# Supply.net
KiCad netlist of a schematic drawn in Altium Designer
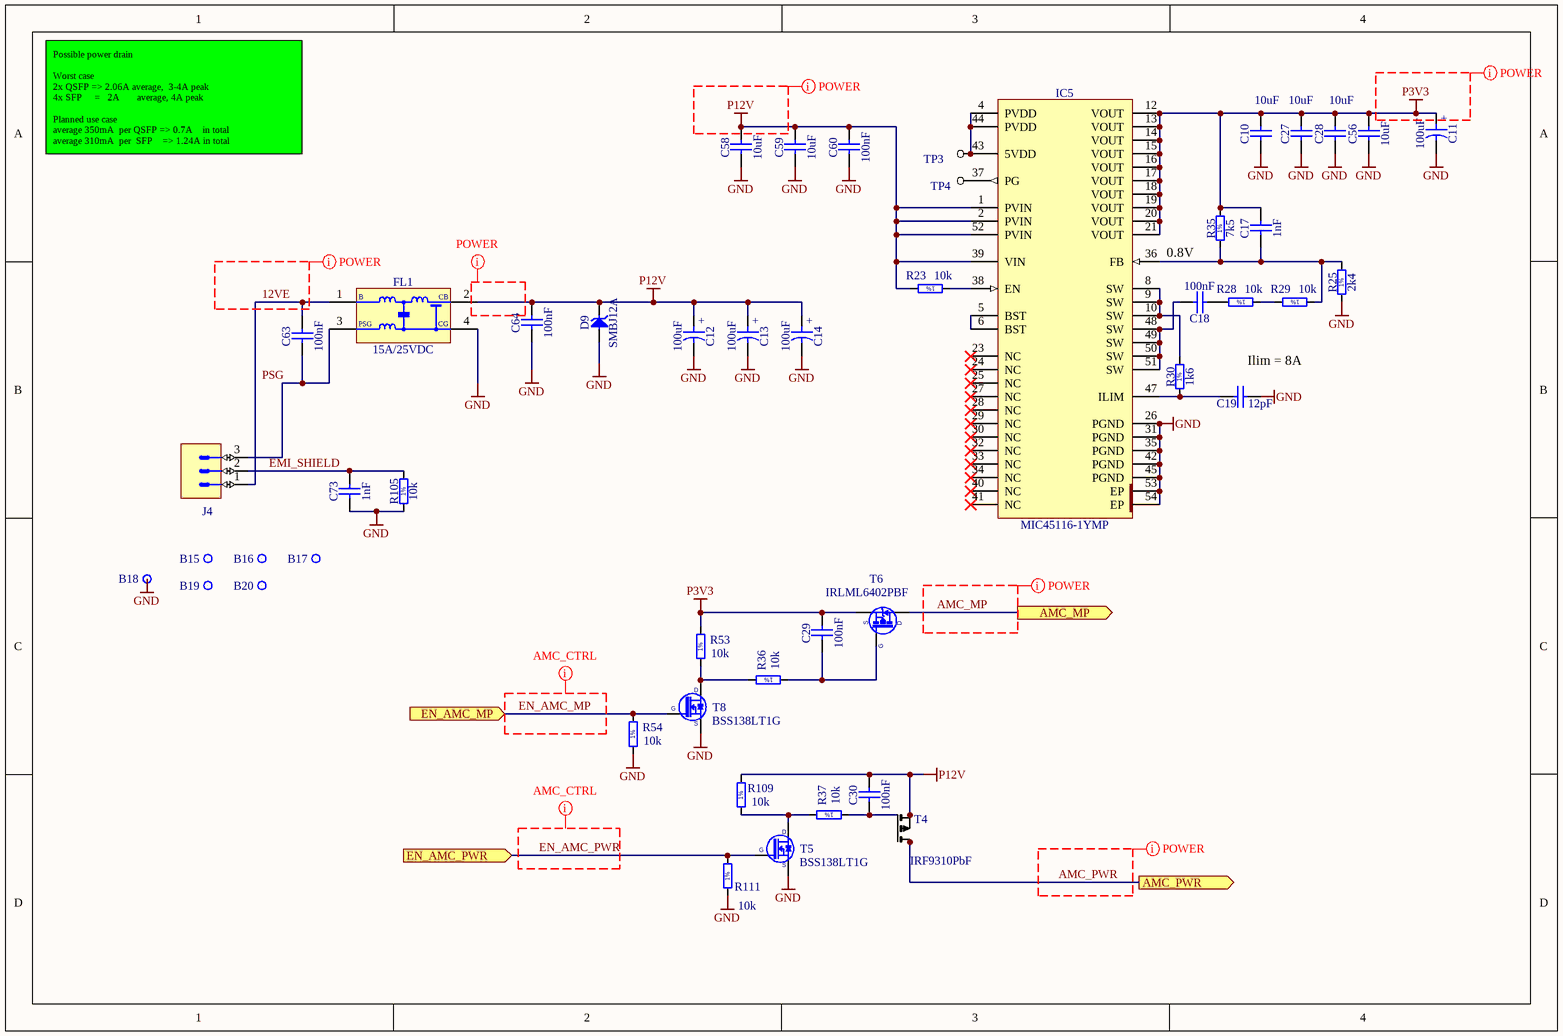
[diagram p0: Supply.SchDoc]

(export (version "E")
  (design (tool "Eeschema 10.0.6"))
  (components
    (comp (ref "B15")
      (value "Plated Hole")
      (footprint "MTG320_550")
      (description "Single Terminal Socket")
      (fields (field (name "PART NUMBER") "PLATED_HOLE3.2_PAD5.5") (field (name "AUTHOR") "CERN DEM JMW"))
      (libsource (lib "Eletro-mechanical") (part "Single Terminal Socket"))
    )
    (comp (ref "B16")
      (value "Plated Hole")
      (footprint "MTG320_550")
      (description "Single Terminal Socket")
      (fields (field (name "PART NUMBER") "PLATED_HOLE3.2_PAD5.5") (field (name "AUTHOR") "CERN DEM JMW"))
      (libsource (lib "Eletro-mechanical") (part "Single Terminal Socket"))
    )
    (comp (ref "B17")
      (value "Plated Hole")
      (footprint "MTG320_550")
      (description "Single Terminal Socket")
      (fields (field (name "PART NUMBER") "PLATED_HOLE3.2_PAD5.5") (field (name "AUTHOR") "CERN DEM JMW"))
      (libsource (lib "Eletro-mechanical") (part "Single Terminal Socket"))
    )
    (comp (ref "B18")
      (value "Plated Hole")
      (footprint "MTG320_550")
      (description "Single Terminal Socket")
      (fields (field (name "PART NUMBER") "PLATED_HOLE3.2_PAD5.5") (field (name "AUTHOR") "CERN DEM JMW"))
      (libsource (lib "Eletro-mechanical") (part "Single Terminal Socket"))
    )
    (comp (ref "B19")
      (value "Plated Hole")
      (footprint "MTG320_550")
      (description "Single Terminal Socket")
      (fields (field (name "PART NUMBER") "PLATED_HOLE3.2_PAD5.5") (field (name "AUTHOR") "CERN DEM JMW"))
      (libsource (lib "Eletro-mechanical") (part "Single Terminal Socket"))
    )
    (comp (ref "B20")
      (value "Plated Hole")
      (footprint "MTG320_550")
      (description "Single Terminal Socket")
      (fields (field (name "PART NUMBER") "PLATED_HOLE3.2_PAD5.5") (field (name "AUTHOR") "CERN DEM JMW"))
      (libsource (lib "Eletro-mechanical") (part "Single Terminal Socket"))
    )
    (comp (ref "C10")
      (value "10uF")
      (footprint "CAPC2012X135N")
      (description "Non-polarised capacitor")
      (fields
        (field (name "PART NUMBER") "CC0805_10UF_10V_10%_X7R")
        (field (name "VOLTAGE") "10V")
        (field (name "AUTHOR") "CERN DEM JLC")
      )
      (libsource (lib "Capacitors") (part "Capacitor - non polarized"))
    )
    (comp (ref "C11")
      (value "100uF")
      (footprint "CAPAE660X540N")
      (description "Polarised capacitor")
      (fields
        (field (name "PART NUMBER") "CAE660-540_100UF_16V_20%")
        (field (name "VOLTAGE") "16V")
        (field (name "AUTHOR") "CERN DEM JLC")
      )
      (libsource (lib "Capacitors") (part "Capacitor - polarized"))
    )
    (comp (ref "C12")
      (value "100uF")
      (footprint "CAPAE660X540N")
      (description "Polarised capacitor")
      (fields
        (field (name "PART NUMBER") "CAE660-540_100UF_16V_20%")
        (field (name "VOLTAGE") "16V")
        (field (name "AUTHOR") "CERN DEM JLC")
      )
      (libsource (lib "Capacitors") (part "Capacitor - polarized"))
    )
    (comp (ref "C13")
      (value "100uF")
      (footprint "CAPAE660X540N")
      (description "Polarised capacitor")
      (fields
        (field (name "PART NUMBER") "CAE660-540_100UF_16V_20%")
        (field (name "VOLTAGE") "16V")
        (field (name "AUTHOR") "CERN DEM JLC")
      )
      (libsource (lib "Capacitors") (part "Capacitor - polarized"))
    )
    (comp (ref "C14")
      (value "100uF")
      (footprint "CAPAE660X540N")
      (description "Polarised capacitor")
      (fields
        (field (name "PART NUMBER") "CAE660-540_100UF_16V_20%")
        (field (name "VOLTAGE") "16V")
        (field (name "AUTHOR") "CERN DEM JLC")
      )
      (libsource (lib "Capacitors") (part "Capacitor - polarized"))
    )
    (comp (ref "C17")
      (value "1nF")
      (footprint "CAPC1005X55N")
      (description "Non-polarised capacitor")
      (fields
        (field (name "PART NUMBER") "CC0402_1NF_50V_10%_X7R")
        (field (name "VOLTAGE") "50V")
        (field (name "AUTHOR") "CERN DEM JLC")
      )
      (libsource (lib "Capacitors") (part "Capacitor - non polarized"))
    )
    (comp (ref "C18")
      (value "100nF")
      (footprint "CAPC1005X55N")
      (description "Non-polarised capacitor")
      (fields
        (field (name "PART NUMBER") "CC0402_100NF_16V_10%_X5R")
        (field (name "VOLTAGE") "16V")
        (field (name "AUTHOR") "CERN DEM JLC")
      )
      (libsource (lib "Capacitors") (part "Capacitor - non polarized"))
    )
    (comp (ref "C19")
      (value "12pF")
      (footprint "CAPC1005X55N")
      (description "Non-polarised capacitor")
      (fields
        (field (name "PART NUMBER") "CC0402_12PF_50V_5%_C0G")
        (field (name "VOLTAGE") "50V")
        (field (name "AUTHOR") "CERN DEM JLC")
      )
      (libsource (lib "Capacitors") (part "Capacitor - non polarized"))
    )
    (comp (ref "C27")
      (value "10uF")
      (footprint "CAPC2012X135N")
      (description "Non-polarised capacitor")
      (fields
        (field (name "PART NUMBER") "CC0805_10UF_10V_10%_X7R")
        (field (name "VOLTAGE") "10V")
        (field (name "AUTHOR") "CERN DEM JLC")
      )
      (libsource (lib "Capacitors") (part "Capacitor - non polarized"))
    )
    (comp (ref "C28")
      (value "10uF")
      (footprint "CAPC2012X135N")
      (description "Non-polarised capacitor")
      (fields
        (field (name "PART NUMBER") "CC0805_10UF_10V_10%_X7R")
        (field (name "VOLTAGE") "10V")
        (field (name "AUTHOR") "CERN DEM JLC")
      )
      (libsource (lib "Capacitors") (part "Capacitor - non polarized"))
    )
    (comp (ref "C29")
      (value "100nF")
      (footprint "CAPC1005X55N")
      (description "Non-polarised capacitor")
      (fields
        (field (name "PART NUMBER") "CC0402_100NF_16V_10%_X5R")
        (field (name "VOLTAGE") "16V")
        (field (name "AUTHOR") "CERN DEM JLC")
      )
      (libsource (lib "Capacitors") (part "Capacitor - non polarized"))
    )
    (comp (ref "C30")
      (value "100nF")
      (footprint "CAPC1005X55N")
      (description "Non-polarised capacitor")
      (fields
        (field (name "PART NUMBER") "CC0402_100NF_16V_10%_X5R")
        (field (name "VOLTAGE") "16V")
        (field (name "AUTHOR") "CERN DEM JLC")
      )
      (libsource (lib "Capacitors") (part "Capacitor - non polarized"))
    )
    (comp (ref "C56")
      (value "10uF")
      (footprint "CAPC2012X135N")
      (description "Non-polarised capacitor")
      (fields
        (field (name "PART NUMBER") "CC0805_10UF_10V_10%_X7R")
        (field (name "VOLTAGE") "10V")
        (field (name "AUTHOR") "CERN DEM JLC")
      )
      (libsource (lib "Capacitors") (part "Capacitor - non polarized"))
    )
    (comp (ref "C58")
      (value "10uF")
      (footprint "CAPC3216X140N")
      (description "Non-polarised capacitor")
      (fields
        (field (name "PART NUMBER") "CC1206_10UF_16V_10%_X7R")
        (field (name "VOLTAGE") "16V")
        (field (name "AUTHOR") "CERN DEM JLC")
      )
      (libsource (lib "Capacitors") (part "Capacitor - non polarized"))
    )
    (comp (ref "C59")
      (value "10uF")
      (footprint "CAPC3216X140N")
      (description "Non-polarised capacitor")
      (fields
        (field (name "PART NUMBER") "CC1206_10UF_16V_10%_X7R")
        (field (name "VOLTAGE") "16V")
        (field (name "AUTHOR") "CERN DEM JLC")
      )
      (libsource (lib "Capacitors") (part "Capacitor - non polarized"))
    )
    (comp (ref "C60")
      (value "100nF")
      (footprint "CAPC1005X55N")
      (description "Non-polarised capacitor")
      (fields
        (field (name "PART NUMBER") "CC0402_100NF_16V_10%_X5R")
        (field (name "VOLTAGE") "16V")
        (field (name "AUTHOR") "CERN DEM JLC")
      )
      (libsource (lib "Capacitors") (part "Capacitor - non polarized"))
    )
    (comp (ref "C63")
      (value "100nF")
      (footprint "CAPC1005X55N")
      (description "Non-polarised capacitor")
      (fields
        (field (name "PART NUMBER") "CC0402_100NF_16V_10%_X5R")
        (field (name "VOLTAGE") "16V")
        (field (name "AUTHOR") "CERN DEM JLC")
      )
      (libsource (lib "Capacitors") (part "Capacitor - non polarized"))
    )
    (comp (ref "C64")
      (value "100nF")
      (footprint "CAPC1005X55N")
      (description "Non-polarised capacitor")
      (fields
        (field (name "PART NUMBER") "CC0402_100NF_16V_10%_X5R")
        (field (name "VOLTAGE") "16V")
        (field (name "AUTHOR") "CERN DEM JLC")
      )
      (libsource (lib "Capacitors") (part "Capacitor - non polarized"))
    )
    (comp (ref "C73")
      (value "1nF")
      (footprint "CAPC1005X55N")
      (description "Non-polarised capacitor")
      (fields
        (field (name "PART NUMBER") "CC0402_1NF_50V_10%_X7R")
        (field (name "VOLTAGE") "50V")
        (field (name "AUTHOR") "CERN DEM JLC")
      )
      (libsource (lib "Capacitors") (part "Capacitor - non polarized"))
    )
    (comp (ref "D9")
      (value "SMBJ12A")
      (footprint "DIOM5336X265N")
      (description "Zener Diode")
      (fields
        (field (name "VOLTAGE") "12V")
        (field (name "POWER") "600W")
        (field (name "AUTHOR") "CERN DEM JLC")
      )
      (libsource (lib "ICs And Semiconductors") (part "Diode Zener"))
    )
    (comp (ref "FL1")
      (value "15A/25VDC")
      (footprint "FIL_MURATA_BNX016")
      (description "Block Type EMIFIL (LC Combined) SMD Type, BNX01* Serie")
      (fields
        (field (name "PART NUMBER") "FIL_MURATA_BNX016-01")
        (field (name "MANUFACTURER") "MURATA")
        (field (name "AUTHOR") "CERN DEM JLC")
      )
      (libsource (lib "Inductors & Transformers") (part "FIL_MURATA_BNX016"))
    )
    (comp (ref "IC5")
      (value "MIC45116-1YMP")
      (footprint "MICROCHIP_H3QFN88-52LD-PL-3")
      (description "0.8V to 85% PVIN (4.75-19V), 6A Synchronous Step-Down Regulator Module")
      (fields (field (name "MANUFACTURER") "MICROCHIP TECHNOLOGY") (field (name "AUTHOR") "CERN DEM JMW"))
      (libsource (lib "ICs And Semiconductors") (part "MIC45116"))
    )
    (comp (ref "J4")
      (value "~")
      (footprint "PHOENIX_1755749")
      (description "Connector 3 Male")
      (fields
        (field (name "PART NUMBER") "PHOENIX_1755749")
        (field (name "MANUFACTURER") "PHOENIX CONTACT")
        (field (name "AUTHOR") "CERN DEM JLC")
      )
      (libsource (lib "Connectors") (part "Connector 3 Male"))
    )
    (comp (ref "R23")
      (value "10k")
      (footprint "RESC1005X40N")
      (description "Resistor - 1%")
      (fields
        (field (name "PART NUMBER") "R0402_10K_1%_0.0625W_100PPM")
        (field (name "POWER") "0.0625W")
        (field (name "AUTHOR") "CERN DEM JLC")
      )
      (libsource (lib "Resistors") (part "Resistor - 1%"))
    )
    (comp (ref "R25")
      (value "2k4")
      (footprint "RESC1005X40N")
      (description "Resistor - 1%")
      (fields
        (field (name "PART NUMBER") "R0402_2K4_1%_0.0625W_100PPM")
        (field (name "POWER") "0.0625W")
        (field (name "AUTHOR") "CERN DEM JLC")
      )
      (libsource (lib "Resistors") (part "Resistor - 1%"))
    )
    (comp (ref "R28")
      (value "10k")
      (footprint "RESC1005X40N")
      (description "Resistor - 1%")
      (fields
        (field (name "PART NUMBER") "R0402_10K_1%_0.0625W_100PPM")
        (field (name "POWER") "0.0625W")
        (field (name "AUTHOR") "CERN DEM JLC")
      )
      (libsource (lib "Resistors") (part "Resistor - 1%"))
    )
    (comp (ref "R29")
      (value "10k")
      (footprint "RESC1005X40N")
      (description "Resistor - 1%")
      (fields
        (field (name "PART NUMBER") "R0402_10K_1%_0.0625W_100PPM")
        (field (name "POWER") "0.0625W")
        (field (name "AUTHOR") "CERN DEM JLC")
      )
      (libsource (lib "Resistors") (part "Resistor - 1%"))
    )
    (comp (ref "R30")
      (value "1k6")
      (footprint "RESC1005X40N")
      (description "Resistor - 1%")
      (fields
        (field (name "PART NUMBER") "R0402_1K6_1%_0.0625W_100PPM")
        (field (name "POWER") "0.0625W")
        (field (name "AUTHOR") "CERN DEM JLC")
      )
      (libsource (lib "Resistors") (part "Resistor - 1%"))
    )
    (comp (ref "R35")
      (value "7k5")
      (footprint "RESC1005X40N")
      (description "Resistor - 1%")
      (fields
        (field (name "PART NUMBER") "R0402_7K5_1%_0.0625W_100PPM")
        (field (name "POWER") "0.0625W")
        (field (name "AUTHOR") "CERN DEM JLC")
      )
      (libsource (lib "Resistors") (part "Resistor - 1%"))
    )
    (comp (ref "R36")
      (value "10k")
      (footprint "RESC1005X40N")
      (description "Resistor - 1%")
      (fields
        (field (name "PART NUMBER") "R0402_10K_1%_0.0625W_100PPM")
        (field (name "POWER") "0.0625W")
        (field (name "AUTHOR") "CERN DEM JLC")
      )
      (libsource (lib "Resistors") (part "Resistor - 1%"))
    )
    (comp (ref "R37")
      (value "10k")
      (footprint "RESC1005X40N")
      (description "Resistor - 1%")
      (fields
        (field (name "PART NUMBER") "R0402_10K_1%_0.0625W_100PPM")
        (field (name "POWER") "0.0625W")
        (field (name "AUTHOR") "CERN DEM JLC")
      )
      (libsource (lib "Resistors") (part "Resistor - 1%"))
    )
    (comp (ref "R53")
      (value "10k")
      (footprint "RESC1005X40N")
      (description "Resistor - 1%")
      (fields
        (field (name "PART NUMBER") "R0402_10K_1%_0.0625W_100PPM")
        (field (name "POWER") "0.0625W")
        (field (name "AUTHOR") "CERN DEM JLC")
      )
      (libsource (lib "Resistors") (part "Resistor - 1%"))
    )
    (comp (ref "R54")
      (value "10k")
      (footprint "RESC1005X40N")
      (description "Resistor - 1%")
      (fields
        (field (name "PART NUMBER") "R0402_10K_1%_0.0625W_100PPM")
        (field (name "POWER") "0.0625W")
        (field (name "AUTHOR") "CERN DEM JLC")
      )
      (libsource (lib "Resistors") (part "Resistor - 1%"))
    )
    (comp (ref "R105")
      (value "10k")
      (footprint "RESC1005X40N")
      (description "Resistor - 1%")
      (fields
        (field (name "PART NUMBER") "R0402_10K_1%_0.0625W_100PPM")
        (field (name "POWER") "0.0625W")
        (field (name "AUTHOR") "CERN DEM JLC")
      )
      (libsource (lib "Resistors") (part "Resistor - 1%"))
    )
    (comp (ref "R109")
      (value "10k")
      (footprint "RESC1005X40N")
      (description "Resistor - 1%")
      (fields
        (field (name "PART NUMBER") "R0402_10K_1%_0.0625W_100PPM")
        (field (name "POWER") "0.0625W")
        (field (name "AUTHOR") "CERN DEM JLC")
      )
      (libsource (lib "Resistors") (part "Resistor - 1%"))
    )
    (comp (ref "R111")
      (value "10k")
      (footprint "RESC1005X40N")
      (description "Resistor - 1%")
      (fields
        (field (name "PART NUMBER") "R0402_10K_1%_0.0625W_100PPM")
        (field (name "POWER") "0.0625W")
        (field (name "AUTHOR") "CERN DEM JLC")
      )
      (libsource (lib "Resistors") (part "Resistor - 1%"))
    )
    (comp (ref "T4")
      (value "IRF9310PbF")
      (footprint "so-8")
      (description "PMOS 30V, 4.6mR, 20A, 2.5W")
      (libsource (lib "LIBRARY_SCH") (part "Q_IRF9310"))
    )
    (comp (ref "T5")
      (value "BSS138LT1G")
      (footprint "SOT95P240X110-3N")
      (description "N-CHANNEL MOSFET WITH DIODE")
      (fields (field (name "MANUFACTURER") "ON SEMICONDUCTOR") (field (name "AUTHOR") "CERN DEM JLC"))
      (libsource (lib "ICs And Semiconductors") (part "N-MOSFET-D 1G 2S 3D"))
    )
    (comp (ref "T6")
      (value "IRLML6402PBF")
      (footprint "SOT95P237X112-3N")
      (description "P-CHANNEL MOSFET WITH ZENER DIODE")
      (fields (field (name "MANUFACTURER") "INTERNATIONAL RECTIFIER") (field (name "AUTHOR") "CERN DEM JLC"))
      (libsource (lib "ICs And Semiconductors") (part "P-MOSFET-DZ 1G 2S 3D"))
    )
    (comp (ref "T8")
      (value "BSS138LT1G")
      (footprint "SOT95P240X110-3N")
      (description "N-CHANNEL MOSFET WITH DIODE")
      (fields (field (name "MANUFACTURER") "ON SEMICONDUCTOR") (field (name "AUTHOR") "CERN DEM JLC"))
      (libsource (lib "ICs And Semiconductors") (part "N-MOSFET-D 1G 2S 3D"))
    )
    (comp (ref "TP3")
      (value "TP")
      (footprint "TP")
      (description "Testpoint")
      (libsource (lib "LIBRARY_SCH") (part "TP"))
    )
    (comp (ref "TP4")
      (value "TP")
      (footprint "TP")
      (description "Testpoint")
      (libsource (lib "LIBRARY_SCH") (part "TP"))
    )
  )
  (nets
    (net (code "1") (name "/12VE") (class "Default")
      (node (ref "C63") (pin "2") (pinfunction "2_2") (pintype "passive"))
      (node (ref "FL1") (pin "1") (pinfunction "B_1") (pintype "passive"))
      (node (ref "J4") (pin "1") (pinfunction "1_1") (pintype "bidirectional"))
    )
    (net (code "2") (name "/AMC_MP") (class "Default")
      (node (ref "T6") (pin "3") (pinfunction "D_3") (pintype "passive"))
    )
    (net (code "3") (name "/AMC_PWR") (class "Default")
      (node (ref "T4") (pin "5") (pinfunction "D1_5") (pintype "open_collector"))
      (node (ref "T4") (pin "6") (pinfunction "D1_6") (pintype "open_collector"))
      (node (ref "T4") (pin "7") (pinfunction "D1_7") (pintype "open_collector"))
      (node (ref "T4") (pin "8") (pinfunction "D1_8") (pintype "open_collector"))
    )
    (net (code "4") (name "/EMI_SHIELD") (class "Default")
      (node (ref "C73") (pin "2") (pinfunction "2_2") (pintype "passive"))
      (node (ref "J4") (pin "2") (pinfunction "2_2") (pintype "bidirectional"))
      (node (ref "R105") (pin "2") (pinfunction "2_2") (pintype "passive"))
    )
    (net (code "5") (name "/EN_AMC_MP") (class "Default")
      (node (ref "R54") (pin "2") (pinfunction "2_2") (pintype "passive"))
      (node (ref "T8") (pin "1") (pinfunction "G_1") (pintype "passive"))
    )
    (net (code "6") (name "/EN_AMC_PWR") (class "Default")
      (node (ref "R111") (pin "2") (pinfunction "2_2") (pintype "passive"))
      (node (ref "T5") (pin "1") (pinfunction "G_1") (pintype "passive"))
    )
    (net (code "8") (name "GND") (class "Default")
      (node (ref "B18") (pin "1") (pinfunction "1_1") (pintype "bidirectional"))
      (node (ref "C10") (pin "1") (pinfunction "1_1") (pintype "passive"))
      (node (ref "C11") (pin "2") (pinfunction "2_2") (pintype "passive"))
      (node (ref "C12") (pin "2") (pinfunction "2_2") (pintype "passive"))
      (node (ref "C13") (pin "2") (pinfunction "2_2") (pintype "passive"))
      (node (ref "C14") (pin "2") (pinfunction "2_2") (pintype "passive"))
      (node (ref "C19") (pin "1") (pinfunction "1_1") (pintype "passive"))
      (node (ref "C27") (pin "1") (pinfunction "1_1") (pintype "passive"))
      (node (ref "C28") (pin "1") (pinfunction "1_1") (pintype "passive"))
      (node (ref "C56") (pin "1") (pinfunction "1_1") (pintype "passive"))
      (node (ref "C58") (pin "1") (pinfunction "1_1") (pintype "passive"))
      (node (ref "C59") (pin "1") (pinfunction "1_1") (pintype "passive"))
      (node (ref "C60") (pin "1") (pinfunction "1_1") (pintype "passive"))
      (node (ref "C64") (pin "1") (pinfunction "1_1") (pintype "passive"))
      (node (ref "C73") (pin "1") (pinfunction "1_1") (pintype "passive"))
      (node (ref "D9") (pin "2") (pinfunction "A_2") (pintype "passive"))
      (node (ref "FL1") (pin "4") (pinfunction "CG_4") (pintype "passive"))
      (node (ref "IC5") (pin "26") (pinfunction "PGND_26") (pintype "power_in"))
      (node (ref "IC5") (pin "31") (pinfunction "PGND_31") (pintype "power_in"))
      (node (ref "IC5") (pin "35") (pinfunction "PGND_35") (pintype "power_in"))
      (node (ref "IC5") (pin "42") (pinfunction "PGND_42") (pintype "power_in"))
      (node (ref "IC5") (pin "45") (pinfunction "PGND_45") (pintype "power_in"))
      (node (ref "IC5") (pin "53") (pinfunction "EP_53") (pintype "power_in"))
      (node (ref "IC5") (pin "54") (pinfunction "EP_54") (pintype "power_in"))
      (node (ref "R105") (pin "1") (pinfunction "1_1") (pintype "passive"))
      (node (ref "R111") (pin "1") (pinfunction "1_1") (pintype "passive"))
      (node (ref "R25") (pin "1") (pinfunction "1_1") (pintype "passive"))
      (node (ref "R54") (pin "1") (pinfunction "1_1") (pintype "passive"))
      (node (ref "T5") (pin "2") (pinfunction "S_2") (pintype "passive"))
      (node (ref "T8") (pin "2") (pinfunction "S_2") (pintype "passive"))
    )
    (net (code "9") (name "Net-(C18-Pad1)") (class "Default")
      (node (ref "C18") (pin "1") (pinfunction "1_1") (pintype "passive"))
      (node (ref "R28") (pin "2") (pinfunction "2_2") (pintype "passive"))
    )
    (net (code "10") (name "Net-(C18-Pad2)") (class "Default")
      (node (ref "C18") (pin "2") (pinfunction "2_2") (pintype "passive"))
      (node (ref "IC5") (pin "48") (pinfunction "SW_48") (pintype "passive"))
      (node (ref "IC5") (pin "49") (pinfunction "SW_49") (pintype "passive"))
      (node (ref "IC5") (pin "50") (pinfunction "SW_50") (pintype "passive"))
      (node (ref "IC5") (pin "51") (pinfunction "SW_51") (pintype "passive"))
    )
    (net (code "11") (name "Net-(FL1-PSG)") (class "Default")
      (node (ref "C63") (pin "1") (pinfunction "1_1") (pintype "passive"))
      (node (ref "FL1") (pin "3") (pinfunction "PSG_3") (pintype "passive"))
      (node (ref "J4") (pin "3") (pinfunction "3_3") (pintype "bidirectional"))
    )
    (net (code "12") (name "Net-(IC5-5VDD)") (class "Default")
      (node (ref "IC5") (pin "4") (pinfunction "PVDD_4") (pintype "power_in"))
      (node (ref "IC5") (pin "43") (pinfunction "5VDD_43") (pintype "power_in"))
      (node (ref "IC5") (pin "44") (pinfunction "PVDD_44") (pintype "power_in"))
      (node (ref "TP3") (pin "1") (pintype "passive"))
    )
    (net (code "13") (name "Net-(IC5-BST-Pad5)") (class "Default")
      (node (ref "IC5") (pin "5") (pinfunction "BST_5") (pintype "passive"))
      (node (ref "IC5") (pin "6") (pinfunction "BST_6") (pintype "passive"))
    )
    (net (code "14") (name "Net-(IC5-EN)") (class "Default")
      (node (ref "IC5") (pin "38") (pinfunction "EN_38") (pintype "input"))
      (node (ref "R23") (pin "1") (pinfunction "1_1") (pintype "passive"))
    )
    (net (code "15") (name "Net-(IC5-FB)") (class "Default")
      (node (ref "C17") (pin "1") (pinfunction "1_1") (pintype "passive"))
      (node (ref "IC5") (pin "36") (pinfunction "FB_36") (pintype "input"))
      (node (ref "R25") (pin "2") (pinfunction "2_2") (pintype "passive"))
      (node (ref "R29") (pin "1") (pinfunction "1_1") (pintype "passive"))
      (node (ref "R35") (pin "1") (pinfunction "1_1") (pintype "passive"))
    )
    (net (code "16") (name "Net-(IC5-ILIM)") (class "Default")
      (node (ref "C19") (pin "2") (pinfunction "2_2") (pintype "passive"))
      (node (ref "IC5") (pin "47") (pinfunction "ILIM_47") (pintype "passive"))
      (node (ref "R30") (pin "1") (pinfunction "1_1") (pintype "passive"))
    )
    (net (code "17") (name "Net-(IC5-PG)") (class "Default")
      (node (ref "IC5") (pin "37") (pinfunction "PG_37") (pintype "output"))
      (node (ref "TP4") (pin "1") (pintype "passive"))
    )
    (net (code "18") (name "Net-(IC5-SW-Pad10)") (class "Default")
      (node (ref "IC5") (pin "10") (pinfunction "SW_10") (pintype "passive"))
      (node (ref "IC5") (pin "8") (pinfunction "SW_8") (pintype "passive"))
      (node (ref "IC5") (pin "9") (pinfunction "SW_9") (pintype "passive"))
      (node (ref "R30") (pin "2") (pinfunction "2_2") (pintype "passive"))
    )
    (net (code "19") (name "Net-(R28-Pad1)") (class "Default")
      (node (ref "R28") (pin "1") (pinfunction "1_1") (pintype "passive"))
      (node (ref "R29") (pin "2") (pinfunction "2_2") (pintype "passive"))
    )
    (net (code "20") (name "Net-(T4-G1)") (class "Default")
      (node (ref "C30") (pin "1") (pinfunction "1_1") (pintype "passive"))
      (node (ref "R37") (pin "1") (pinfunction "1_1") (pintype "passive"))
      (node (ref "T4") (pin "4") (pinfunction "G1_4") (pintype "input"))
    )
    (net (code "21") (name "Net-(T5-D)") (class "Default")
      (node (ref "R109") (pin "1") (pinfunction "1_1") (pintype "passive"))
      (node (ref "R37") (pin "2") (pinfunction "2_2") (pintype "passive"))
      (node (ref "T5") (pin "3") (pinfunction "D_3") (pintype "passive"))
    )
    (net (code "22") (name "Net-(T6-G)") (class "Default")
      (node (ref "C29") (pin "1") (pinfunction "1_1") (pintype "passive"))
      (node (ref "R36") (pin "1") (pinfunction "1_1") (pintype "passive"))
      (node (ref "T6") (pin "1") (pinfunction "G_1") (pintype "passive"))
    )
    (net (code "23") (name "Net-(T8-D)") (class "Default")
      (node (ref "R36") (pin "2") (pinfunction "2_2") (pintype "passive"))
      (node (ref "R53") (pin "1") (pinfunction "1_1") (pintype "passive"))
      (node (ref "T8") (pin "3") (pinfunction "D_3") (pintype "passive"))
    )
    (net (code "24") (name "P3V3") (class "Default")
      (node (ref "C10") (pin "2") (pinfunction "2_2") (pintype "passive"))
      (node (ref "C11") (pin "1") (pinfunction "1_1") (pintype "passive"))
      (node (ref "C17") (pin "2") (pinfunction "2_2") (pintype "passive"))
      (node (ref "C27") (pin "2") (pinfunction "2_2") (pintype "passive"))
      (node (ref "C28") (pin "2") (pinfunction "2_2") (pintype "passive"))
      (node (ref "C29") (pin "2") (pinfunction "2_2") (pintype "passive"))
      (node (ref "C56") (pin "2") (pinfunction "2_2") (pintype "passive"))
      (node (ref "IC5") (pin "12") (pinfunction "VOUT_12") (pintype "power_in"))
      (node (ref "IC5") (pin "13") (pinfunction "VOUT_13") (pintype "power_in"))
      (node (ref "IC5") (pin "14") (pinfunction "VOUT_14") (pintype "power_in"))
      (node (ref "IC5") (pin "15") (pinfunction "VOUT_15") (pintype "power_in"))
      (node (ref "IC5") (pin "16") (pinfunction "VOUT_16") (pintype "power_in"))
      (node (ref "IC5") (pin "17") (pinfunction "VOUT_17") (pintype "power_in"))
      (node (ref "IC5") (pin "18") (pinfunction "VOUT_18") (pintype "power_in"))
      (node (ref "IC5") (pin "19") (pinfunction "VOUT_19") (pintype "power_in"))
      (node (ref "IC5") (pin "20") (pinfunction "VOUT_20") (pintype "power_in"))
      (node (ref "IC5") (pin "21") (pinfunction "VOUT_21") (pintype "power_in"))
      (node (ref "R35") (pin "2") (pinfunction "2_2") (pintype "passive"))
      (node (ref "R53") (pin "2") (pinfunction "2_2") (pintype "passive"))
      (node (ref "T6") (pin "2") (pinfunction "S_2") (pintype "passive"))
    )
    (net (code "25") (name "P12V") (class "Default")
      (node (ref "C12") (pin "1") (pinfunction "1_1") (pintype "passive"))
      (node (ref "C13") (pin "1") (pinfunction "1_1") (pintype "passive"))
      (node (ref "C14") (pin "1") (pinfunction "1_1") (pintype "passive"))
      (node (ref "C30") (pin "2") (pinfunction "2_2") (pintype "passive"))
      (node (ref "C58") (pin "2") (pinfunction "2_2") (pintype "passive"))
      (node (ref "C59") (pin "2") (pinfunction "2_2") (pintype "passive"))
      (node (ref "C60") (pin "2") (pinfunction "2_2") (pintype "passive"))
      (node (ref "C64") (pin "2") (pinfunction "2_2") (pintype "passive"))
      (node (ref "D9") (pin "1") (pinfunction "C_1") (pintype "passive"))
      (node (ref "FL1") (pin "2") (pinfunction "CB_2") (pintype "passive"))
      (node (ref "IC5") (pin "1") (pinfunction "PVIN_1") (pintype "power_in"))
      (node (ref "IC5") (pin "2") (pinfunction "PVIN_2") (pintype "power_in"))
      (node (ref "IC5") (pin "39") (pinfunction "VIN_39") (pintype "power_in"))
      (node (ref "IC5") (pin "52") (pinfunction "PVIN_52") (pintype "power_in"))
      (node (ref "R109") (pin "2") (pinfunction "2_2") (pintype "passive"))
      (node (ref "R23") (pin "2") (pinfunction "2_2") (pintype "passive"))
      (node (ref "T4") (pin "1") (pinfunction "S1_1") (pintype "open_emitter"))
      (node (ref "T4") (pin "2") (pinfunction "S1_2") (pintype "open_emitter"))
      (node (ref "T4") (pin "3") (pinfunction "S1_3") (pintype "open_emitter"))
    )
    (net (code "26") (name "unconnected-(B15-Pad1)") (class "Default")
      (node (ref "B15") (pin "1") (pinfunction "1_1") (pintype "bidirectional"))
    )
    (net (code "27") (name "unconnected-(B16-Pad1)") (class "Default")
      (node (ref "B16") (pin "1") (pinfunction "1_1") (pintype "bidirectional"))
    )
    (net (code "28") (name "unconnected-(B17-Pad1)") (class "Default")
      (node (ref "B17") (pin "1") (pinfunction "1_1") (pintype "bidirectional"))
    )
    (net (code "29") (name "unconnected-(B19-Pad1)") (class "Default")
      (node (ref "B19") (pin "1") (pinfunction "1_1") (pintype "bidirectional"))
    )
    (net (code "30") (name "unconnected-(B20-Pad1)") (class "Default")
      (node (ref "B20") (pin "1") (pinfunction "1_1") (pintype "bidirectional"))
    )
    (net (code "31") (name "unconnected-(IC5-NC-Pad23)") (class "Default")
      (node (ref "IC5") (pin "23") (pinfunction "NC_23") (pintype "passive+no_connect"))
    )
    (net (code "32") (name "unconnected-(IC5-NC-Pad24)") (class "Default")
      (node (ref "IC5") (pin "24") (pinfunction "NC_24") (pintype "passive+no_connect"))
    )
    (net (code "33") (name "unconnected-(IC5-NC-Pad25)") (class "Default")
      (node (ref "IC5") (pin "25") (pinfunction "NC_25") (pintype "passive+no_connect"))
    )
    (net (code "34") (name "unconnected-(IC5-NC-Pad27)") (class "Default")
      (node (ref "IC5") (pin "27") (pinfunction "NC_27") (pintype "passive+no_connect"))
    )
    (net (code "35") (name "unconnected-(IC5-NC-Pad28)") (class "Default")
      (node (ref "IC5") (pin "28") (pinfunction "NC_28") (pintype "passive+no_connect"))
    )
    (net (code "36") (name "unconnected-(IC5-NC-Pad29)") (class "Default")
      (node (ref "IC5") (pin "29") (pinfunction "NC_29") (pintype "passive+no_connect"))
    )
    (net (code "37") (name "unconnected-(IC5-NC-Pad30)") (class "Default")
      (node (ref "IC5") (pin "30") (pinfunction "NC_30") (pintype "passive+no_connect"))
    )
    (net (code "38") (name "unconnected-(IC5-NC-Pad32)") (class "Default")
      (node (ref "IC5") (pin "32") (pinfunction "NC_32") (pintype "passive+no_connect"))
    )
    (net (code "39") (name "unconnected-(IC5-NC-Pad33)") (class "Default")
      (node (ref "IC5") (pin "33") (pinfunction "NC_33") (pintype "passive+no_connect"))
    )
    (net (code "40") (name "unconnected-(IC5-NC-Pad34)") (class "Default")
      (node (ref "IC5") (pin "34") (pinfunction "NC_34") (pintype "passive+no_connect"))
    )
    (net (code "41") (name "unconnected-(IC5-NC-Pad40)") (class "Default")
      (node (ref "IC5") (pin "40") (pinfunction "NC_40") (pintype "passive+no_connect"))
    )
    (net (code "42") (name "unconnected-(IC5-NC-Pad41)") (class "Default")
      (node (ref "IC5") (pin "41") (pinfunction "NC_41") (pintype "passive+no_connect"))
    )
  )
)
